# 01-mcu.net
KiCad netlist of a schematic drawn in EAGLE
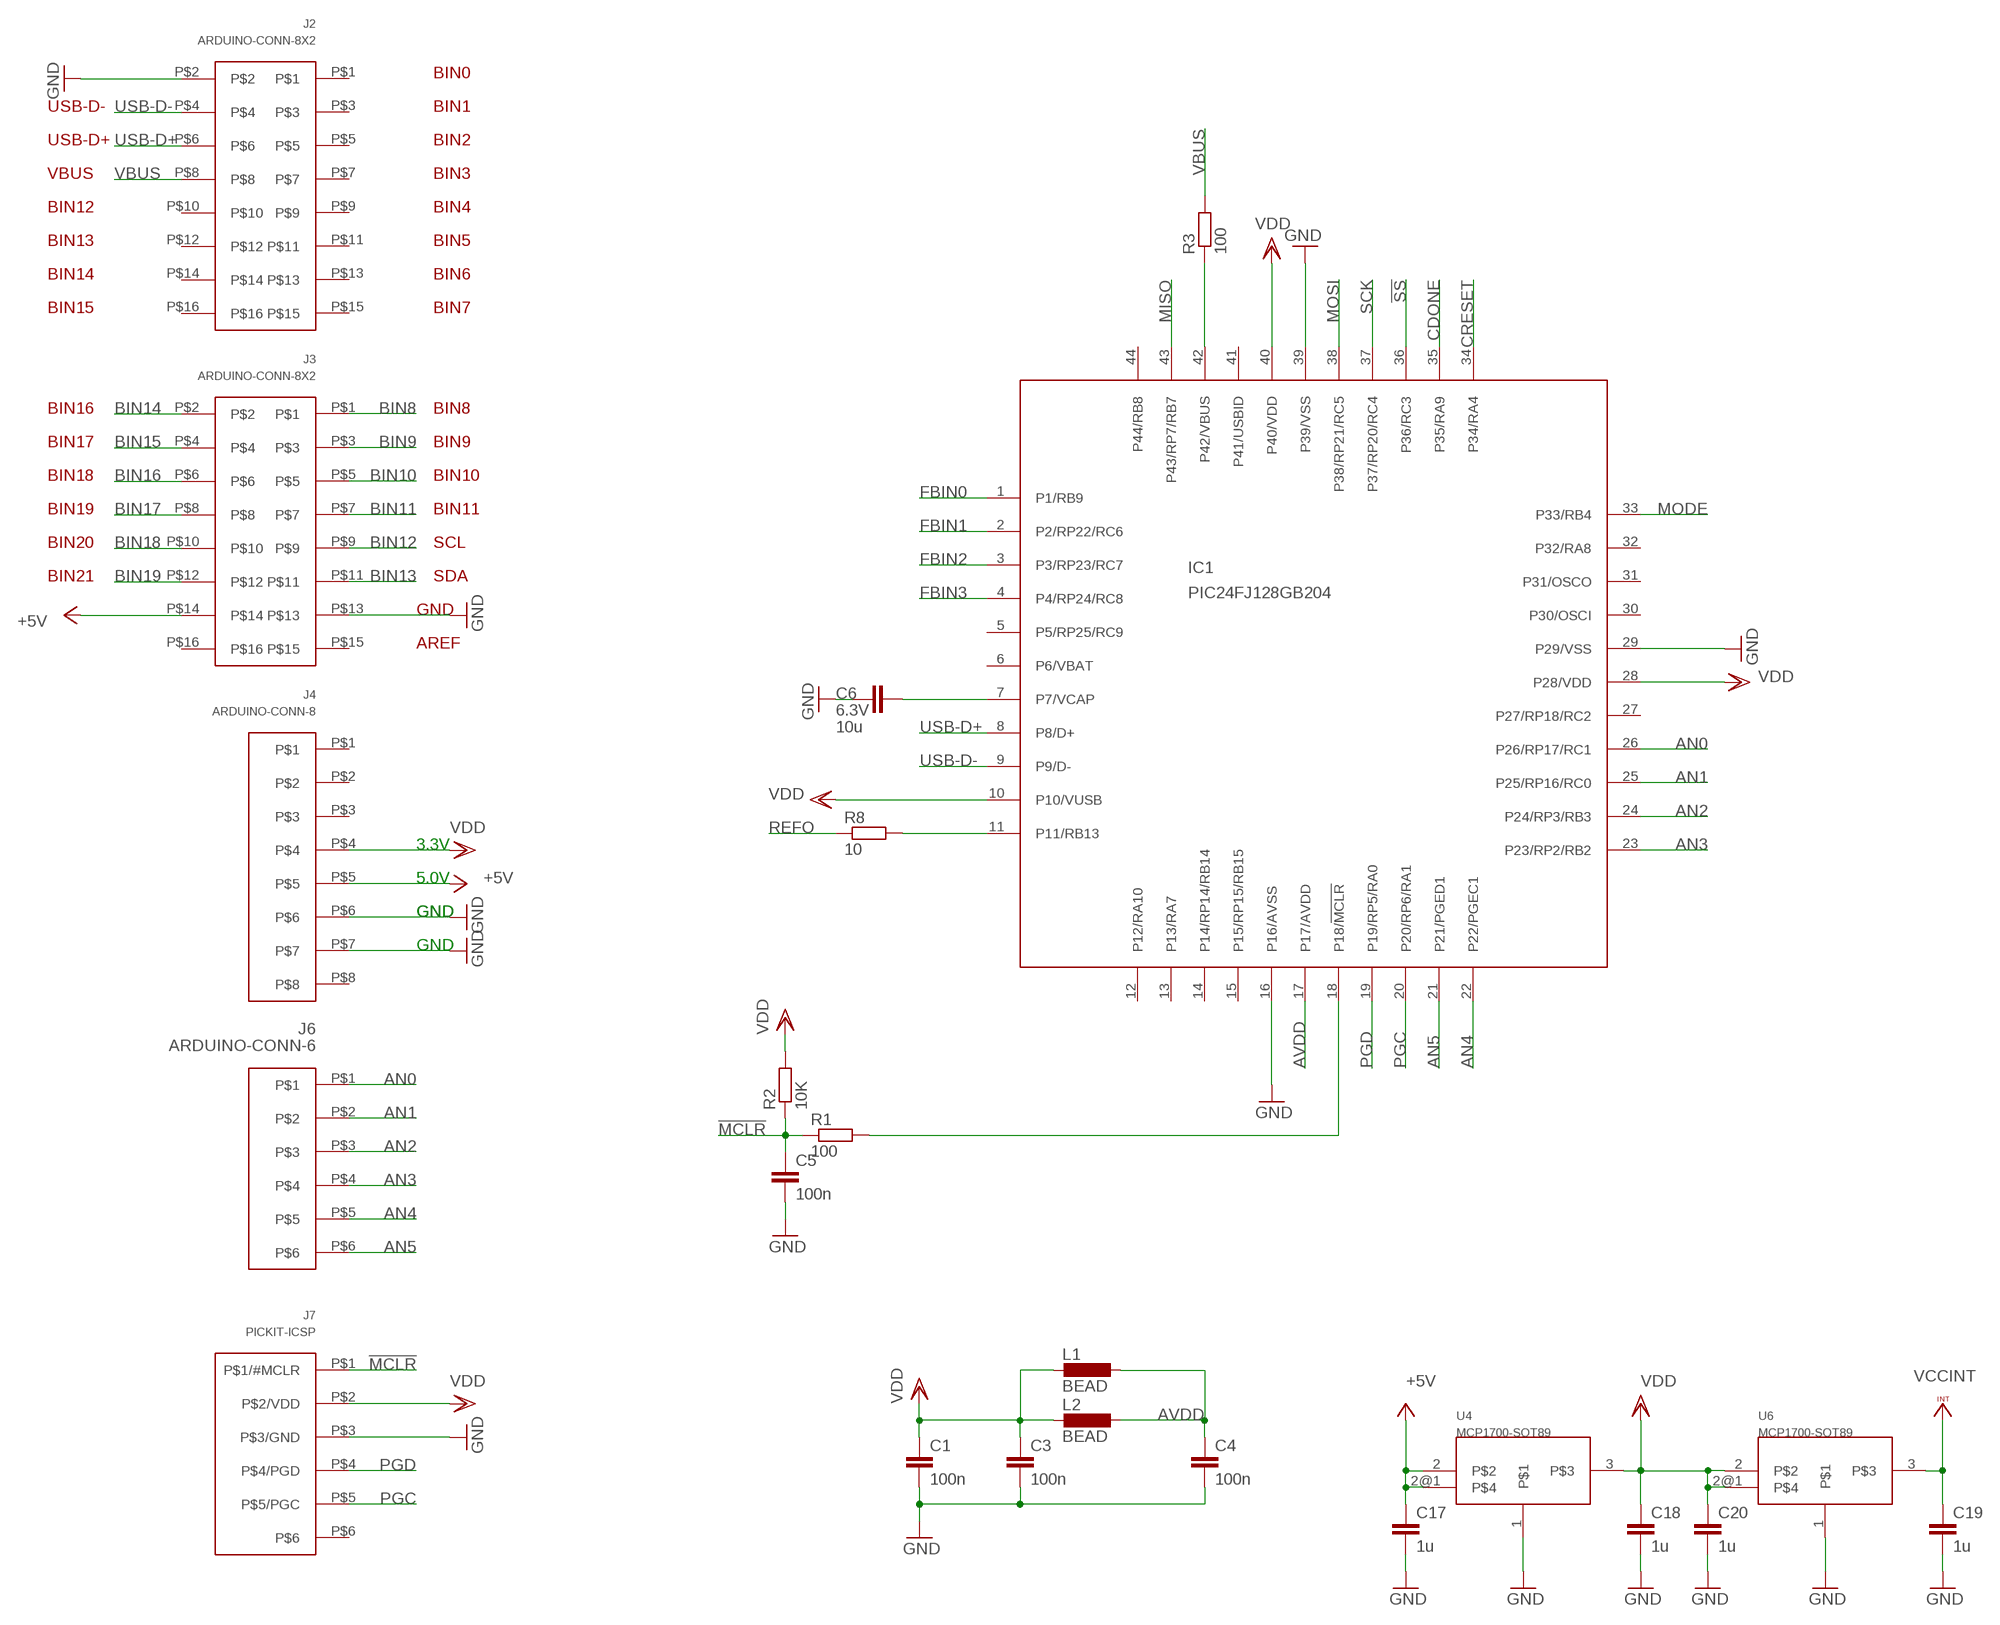
[diagram p0: schematic, sheet 1, part 1 of 2]
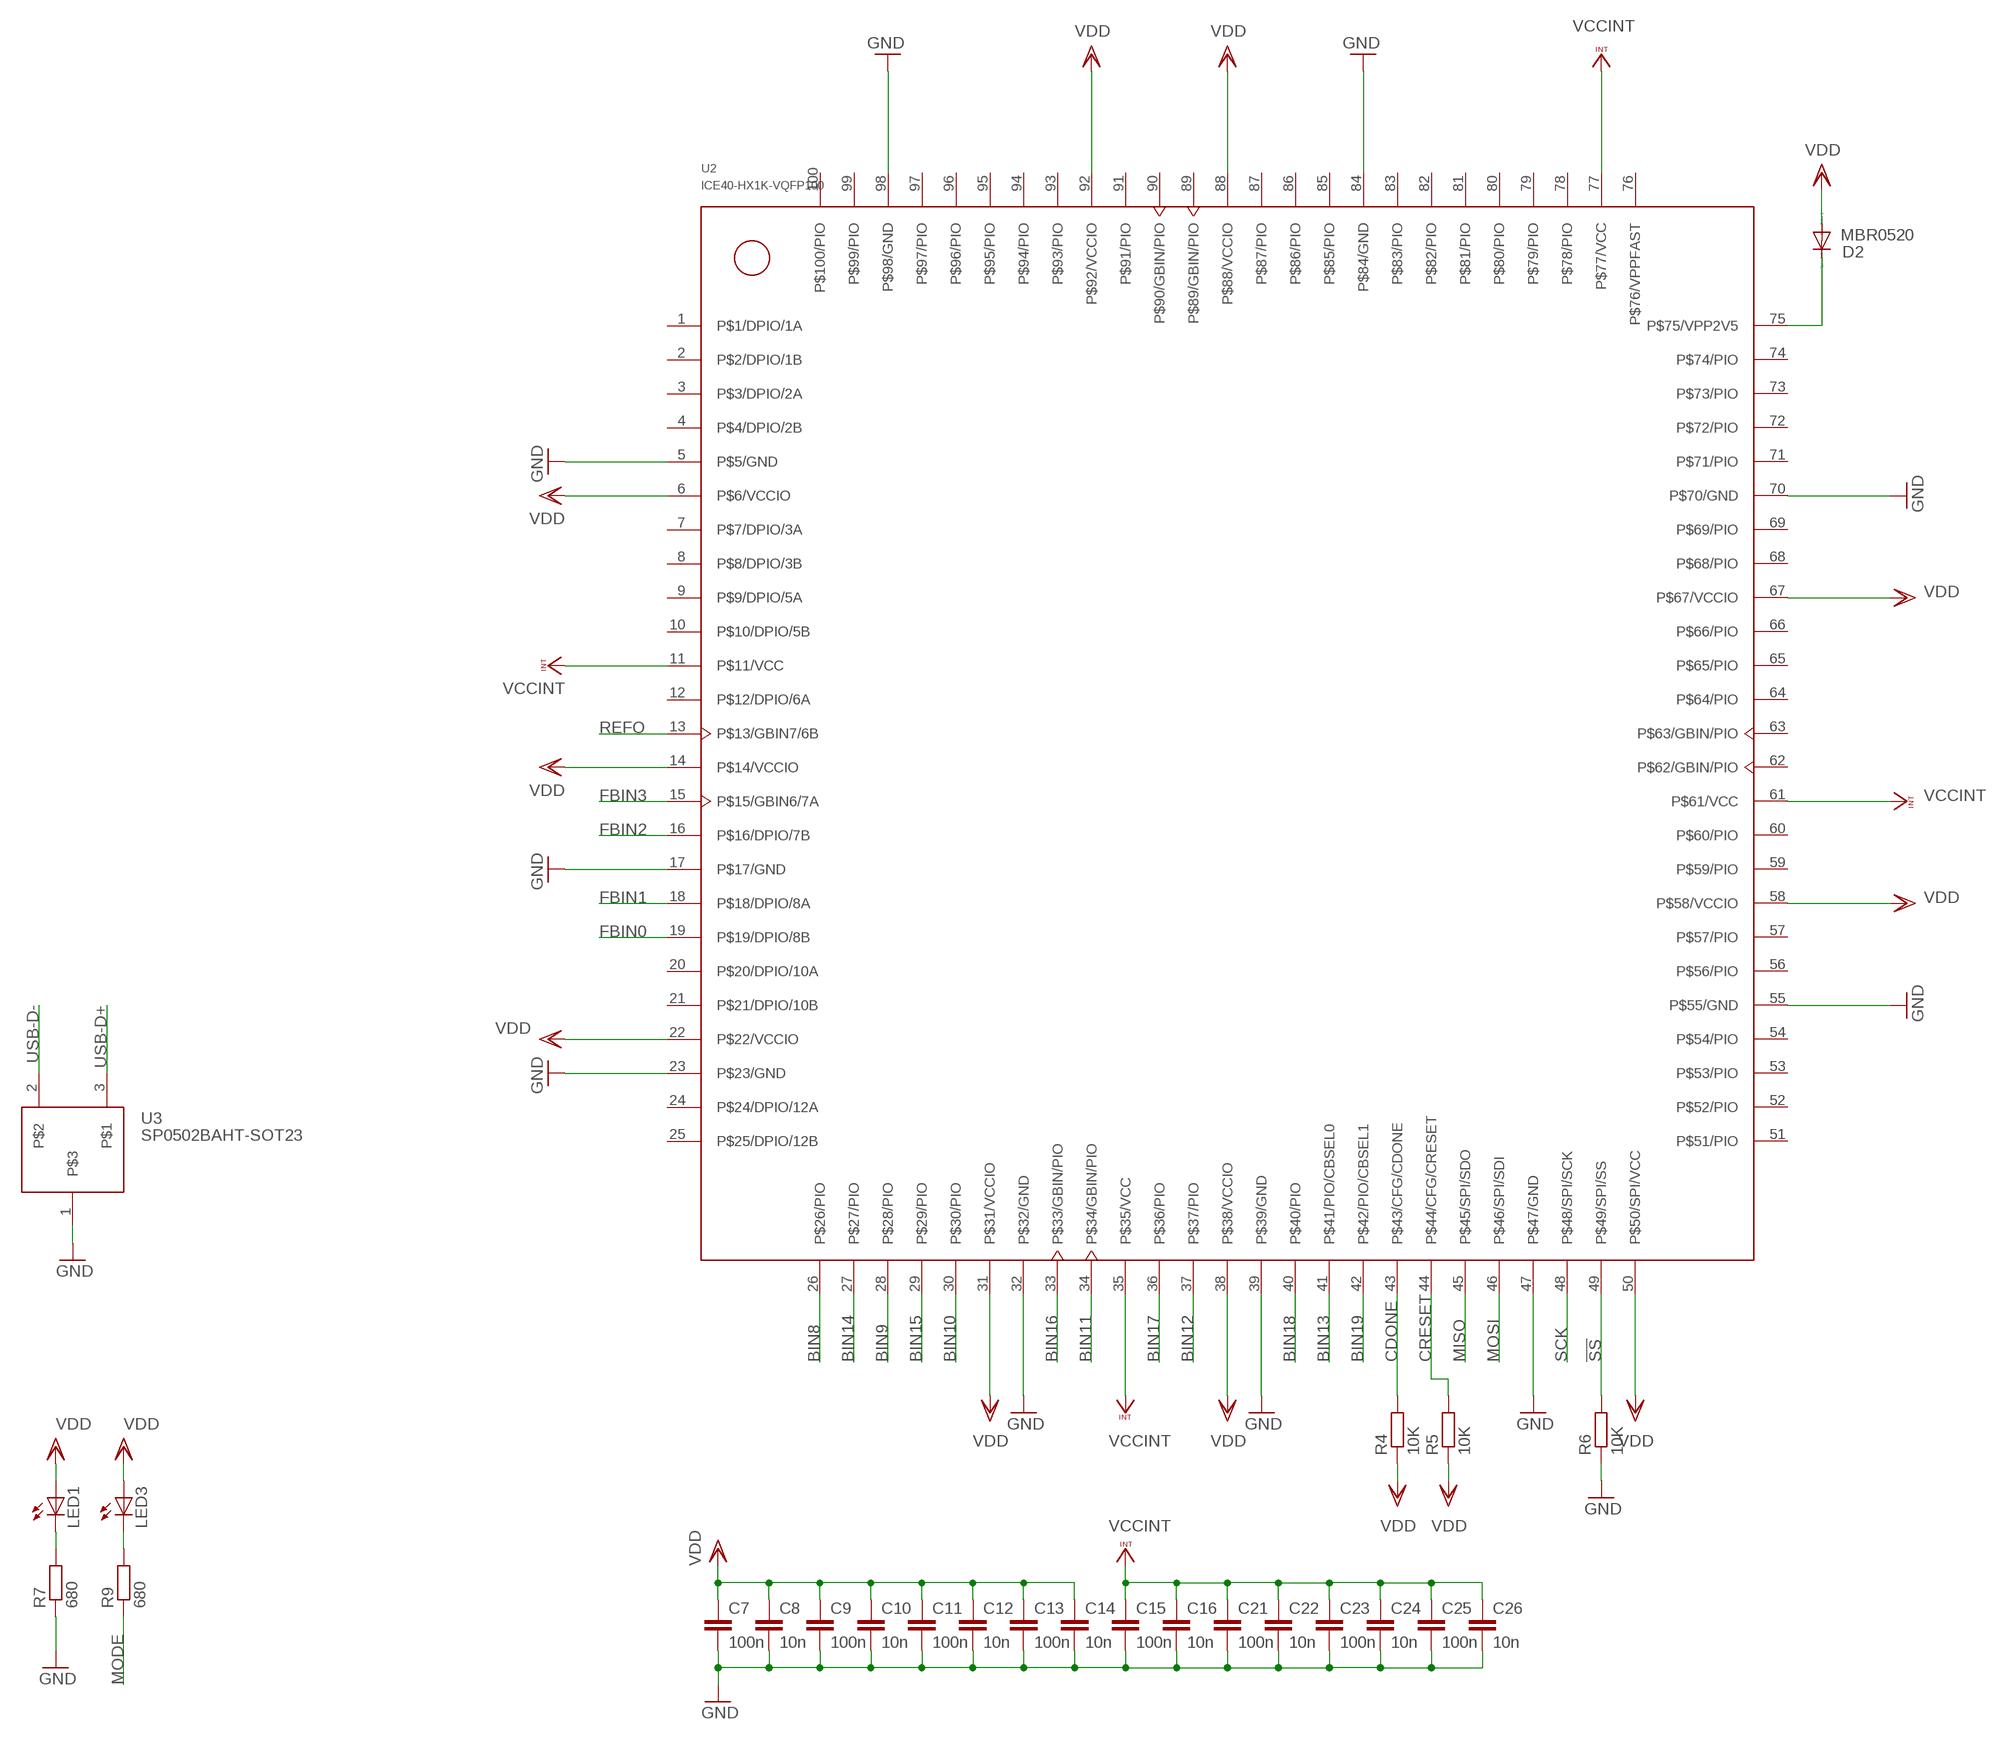
[diagram p1: schematic, sheet 1, part 2 of 2]

(export (version "E")
  (design (tool "Eeschema 10.0.6"))
  (components
    (comp (ref "C1")
      (value "100n")
      (footprint "eagle-import:C0805")
      (libsource (lib "eagle-import") (part "C-EUC0805"))
    )
    (comp (ref "C3")
      (value "100n")
      (footprint "eagle-import:C0805")
      (libsource (lib "eagle-import") (part "C-EUC0805"))
    )
    (comp (ref "C4")
      (value "100n")
      (footprint "eagle-import:C0805")
      (libsource (lib "eagle-import") (part "C-EUC0805"))
    )
    (comp (ref "C5")
      (value "100n")
      (footprint "eagle-import:C0805")
      (libsource (lib "eagle-import") (part "C-EUC0805"))
    )
    (comp (ref "C6")
      (value "10u")
      (footprint "eagle-import:C0805")
      (fields (field (name "RATING") "6.3V"))
      (libsource (lib "eagle-import") (part "C-EUC0805"))
    )
    (comp (ref "C7")
      (value "100n")
      (footprint "eagle-import:C0805")
      (libsource (lib "eagle-import") (part "C-EUC0805"))
    )
    (comp (ref "C8")
      (value "10n")
      (footprint "eagle-import:C0805")
      (libsource (lib "eagle-import") (part "C-EUC0805"))
    )
    (comp (ref "C9")
      (value "100n")
      (footprint "eagle-import:C0805")
      (libsource (lib "eagle-import") (part "C-EUC0805"))
    )
    (comp (ref "C10")
      (value "10n")
      (footprint "eagle-import:C0805")
      (libsource (lib "eagle-import") (part "C-EUC0805"))
    )
    (comp (ref "C11")
      (value "100n")
      (footprint "eagle-import:C0805")
      (libsource (lib "eagle-import") (part "C-EUC0805"))
    )
    (comp (ref "C12")
      (value "10n")
      (footprint "eagle-import:C0805")
      (libsource (lib "eagle-import") (part "C-EUC0805"))
    )
    (comp (ref "C13")
      (value "100n")
      (footprint "eagle-import:C0805")
      (libsource (lib "eagle-import") (part "C-EUC0805"))
    )
    (comp (ref "C14")
      (value "10n")
      (footprint "eagle-import:C0805")
      (libsource (lib "eagle-import") (part "C-EUC0805"))
    )
    (comp (ref "C15")
      (value "100n")
      (footprint "eagle-import:C0805")
      (libsource (lib "eagle-import") (part "C-EUC0805"))
    )
    (comp (ref "C16")
      (value "10n")
      (footprint "eagle-import:C0805")
      (libsource (lib "eagle-import") (part "C-EUC0805"))
    )
    (comp (ref "C17")
      (value "1u")
      (footprint "eagle-import:C0805")
      (libsource (lib "eagle-import") (part "C-EUC0805"))
    )
    (comp (ref "C18")
      (value "1u")
      (footprint "eagle-import:C0805")
      (libsource (lib "eagle-import") (part "C-EUC0805"))
    )
    (comp (ref "C19")
      (value "1u")
      (footprint "eagle-import:C0805")
      (libsource (lib "eagle-import") (part "C-EUC0805"))
    )
    (comp (ref "C20")
      (value "1u")
      (footprint "eagle-import:C0805")
      (libsource (lib "eagle-import") (part "C-EUC0805"))
    )
    (comp (ref "C21")
      (value "100n")
      (footprint "eagle-import:C0805")
      (libsource (lib "eagle-import") (part "C-EUC0805"))
    )
    (comp (ref "C22")
      (value "10n")
      (footprint "eagle-import:C0805")
      (libsource (lib "eagle-import") (part "C-EUC0805"))
    )
    (comp (ref "C23")
      (value "100n")
      (footprint "eagle-import:C0805")
      (libsource (lib "eagle-import") (part "C-EUC0805"))
    )
    (comp (ref "C24")
      (value "10n")
      (footprint "eagle-import:C0805")
      (libsource (lib "eagle-import") (part "C-EUC0805"))
    )
    (comp (ref "C25")
      (value "100n")
      (footprint "eagle-import:C0805")
      (libsource (lib "eagle-import") (part "C-EUC0805"))
    )
    (comp (ref "C26")
      (value "10n")
      (footprint "eagle-import:C0805")
      (libsource (lib "eagle-import") (part "C-EUC0805"))
    )
    (comp (ref "D2")
      (value "MBR0520")
      (footprint "eagle-import:MBR0520-SOD-123_MINI-SMA")
      (libsource (lib "eagle-import") (part "MBR0520"))
    )
    (comp (ref "IC1")
      (value "PIC24FJ128GB204")
      (footprint "eagle-import:TQFP44")
      (libsource (lib "eagle-import") (part "PIC24FJ128GB204"))
    )
    (comp (ref "J2")
      (value "ARDUINO-CONN-8X2")
      (footprint "eagle-import:ARDUINO-CONN-8X2")
      (libsource (lib "eagle-import") (part "ARDUINO-CONN-8X2"))
    )
    (comp (ref "J3")
      (value "ARDUINO-CONN-8X2")
      (footprint "eagle-import:ARDUINO-CONN-8X2")
      (libsource (lib "eagle-import") (part "ARDUINO-CONN-8X2"))
    )
    (comp (ref "J4")
      (value "ARDUINO-CONN-8")
      (footprint "eagle-import:ARDUINO-CONN-8")
      (libsource (lib "eagle-import") (part "ARDUINO-CONN-8"))
    )
    (comp (ref "J6")
      (value "ARDUINO-CONN-6")
      (footprint "eagle-import:ARDUINO-CONN-6")
      (libsource (lib "eagle-import") (part "ARDUINO-CONN-6"))
    )
    (comp (ref "J7")
      (value "PICKIT-ICSP")
      (footprint "eagle-import:PICKIT-ICSP")
      (libsource (lib "eagle-import") (part "PICKIT-ICSP"))
    )
    (comp (ref "L1")
      (value "BEAD")
      (footprint "eagle-import:L0805")
      (libsource (lib "eagle-import") (part "BEAD"))
    )
    (comp (ref "L2")
      (value "BEAD")
      (footprint "eagle-import:L0805")
      (libsource (lib "eagle-import") (part "BEAD"))
    )
    (comp (ref "LED1")
      (value "LEDCHIP-LED0805")
      (footprint "eagle-import:CHIP-LED0805")
      (libsource (lib "eagle-import") (part "LEDCHIP-LED0805"))
    )
    (comp (ref "LED3")
      (value "LEDCHIP-LED0805")
      (footprint "eagle-import:CHIP-LED0805")
      (libsource (lib "eagle-import") (part "LEDCHIP-LED0805"))
    )
    (comp (ref "R1")
      (value "100")
      (footprint "eagle-import:R0805")
      (libsource (lib "eagle-import") (part "R-EU_R0805"))
    )
    (comp (ref "R2")
      (value "10K")
      (footprint "eagle-import:R0805")
      (libsource (lib "eagle-import") (part "R-EU_R0805"))
    )
    (comp (ref "R3")
      (value "100")
      (footprint "eagle-import:R0805")
      (libsource (lib "eagle-import") (part "R-EU_R0805"))
    )
    (comp (ref "R4")
      (value "10K")
      (footprint "eagle-import:R0805")
      (libsource (lib "eagle-import") (part "R-EU_R0805"))
    )
    (comp (ref "R5")
      (value "10K")
      (footprint "eagle-import:R0805")
      (libsource (lib "eagle-import") (part "R-EU_R0805"))
    )
    (comp (ref "R6")
      (value "10K")
      (footprint "eagle-import:R0805")
      (libsource (lib "eagle-import") (part "R-EU_R0805"))
    )
    (comp (ref "R7")
      (value "680")
      (footprint "eagle-import:R0805")
      (libsource (lib "eagle-import") (part "R-EU_R0805"))
    )
    (comp (ref "R8")
      (value "10")
      (footprint "eagle-import:R0805")
      (libsource (lib "eagle-import") (part "R-EU_R0805"))
    )
    (comp (ref "R9")
      (value "680")
      (footprint "eagle-import:R0805")
      (libsource (lib "eagle-import") (part "R-EU_R0805"))
    )
    (comp (ref "U2")
      (value "ICE40-HX1K-VQFP100")
      (footprint "eagle-import:TQFP100-14X14")
      (libsource (lib "eagle-import") (part "ICE40-HX1K-VQFP100"))
    )
    (comp (ref "U3")
      (value "SP0502BAHT-SOT23")
      (footprint "eagle-import:SOT23")
      (libsource (lib "eagle-import") (part "SP0502BAHT-SOT23"))
    )
    (comp (ref "U4")
      (value "MCP1700-SOT89")
      (footprint "eagle-import:MCP1700-SOT89")
      (libsource (lib "eagle-import") (part "MCP1700-SOT89"))
    )
    (comp (ref "U6")
      (value "MCP1700-SOT89")
      (footprint "eagle-import:MCP1700-SOT89")
      (libsource (lib "eagle-import") (part "MCP1700-SOT89"))
    )
  )
  (nets
    (net (code "1") (name "+5V") (class "Default")
      (node (ref "C17") (pin "1") (pinfunction "1_1") (pintype "passive"))
      (node (ref "J3") (pin "P$14") (pinfunction "P$14_P$14") (pintype "bidirectional"))
      (node (ref "J4") (pin "P$5") (pinfunction "P$5_P$5") (pintype "bidirectional"))
      (node (ref "U4") (pin "2") (pinfunction "P$2_2") (pintype "bidirectional"))
      (node (ref "U4") (pin "2@1") (pinfunction "P$4_2@1") (pintype "bidirectional"))
    )
    (net (code "2") (name "/AN0") (class "Default")
      (node (ref "IC1") (pin "26") (pinfunction "P26/RP17/RC1_26") (pintype "bidirectional"))
      (node (ref "J6") (pin "P$1") (pinfunction "P$1_P$1") (pintype "bidirectional"))
    )
    (net (code "3") (name "/AN1") (class "Default")
      (node (ref "IC1") (pin "25") (pinfunction "P25/RP16/RC0_25") (pintype "bidirectional"))
      (node (ref "J6") (pin "P$2") (pinfunction "P$2_P$2") (pintype "bidirectional"))
    )
    (net (code "4") (name "/AN2") (class "Default")
      (node (ref "IC1") (pin "24") (pinfunction "P24/RP3/RB3_24") (pintype "bidirectional"))
      (node (ref "J6") (pin "P$3") (pinfunction "P$3_P$3") (pintype "bidirectional"))
    )
    (net (code "5") (name "/AN3") (class "Default")
      (node (ref "IC1") (pin "23") (pinfunction "P23/RP2/RB2_23") (pintype "bidirectional"))
      (node (ref "J6") (pin "P$4") (pinfunction "P$4_P$4") (pintype "bidirectional"))
    )
    (net (code "6") (name "/AN4") (class "Default")
      (node (ref "IC1") (pin "22") (pinfunction "P22/PGEC1_22") (pintype "bidirectional"))
      (node (ref "J6") (pin "P$5") (pinfunction "P$5_P$5") (pintype "bidirectional"))
    )
    (net (code "7") (name "/AN5") (class "Default")
      (node (ref "IC1") (pin "21") (pinfunction "P21/PGED1_21") (pintype "bidirectional"))
      (node (ref "J6") (pin "P$6") (pinfunction "P$6_P$6") (pintype "bidirectional"))
    )
    (net (code "8") (name "/AVDD") (class "Default")
      (node (ref "C4") (pin "1") (pinfunction "1_1") (pintype "passive"))
      (node (ref "IC1") (pin "17") (pinfunction "P17/AVDD_17") (pintype "power_in"))
      (node (ref "L1") (pin "2") (pinfunction "2_2") (pintype "passive"))
      (node (ref "L2") (pin "2") (pinfunction "2_2") (pintype "passive"))
    )
    (net (code "9") (name "/BIN8") (class "Default")
      (node (ref "J3") (pin "P$1") (pinfunction "P$1_P$1") (pintype "bidirectional"))
      (node (ref "U2") (pin "26") (pinfunction "P$26/PIO_26") (pintype "bidirectional"))
    )
    (net (code "10") (name "/BIN9") (class "Default")
      (node (ref "J3") (pin "P$3") (pinfunction "P$3_P$3") (pintype "bidirectional"))
      (node (ref "U2") (pin "28") (pinfunction "P$28/PIO_28") (pintype "bidirectional"))
    )
    (net (code "11") (name "/BIN10") (class "Default")
      (node (ref "J3") (pin "P$5") (pinfunction "P$5_P$5") (pintype "bidirectional"))
      (node (ref "U2") (pin "30") (pinfunction "P$30/PIO_30") (pintype "bidirectional"))
    )
    (net (code "12") (name "/BIN11") (class "Default")
      (node (ref "J3") (pin "P$7") (pinfunction "P$7_P$7") (pintype "bidirectional"))
      (node (ref "U2") (pin "34") (pinfunction "P$34/GBIN/PIO_34") (pintype "bidirectional"))
    )
    (net (code "13") (name "/BIN12") (class "Default")
      (node (ref "J3") (pin "P$9") (pinfunction "P$9_P$9") (pintype "bidirectional"))
      (node (ref "U2") (pin "37") (pinfunction "P$37/PIO_37") (pintype "bidirectional"))
    )
    (net (code "14") (name "/BIN13") (class "Default")
      (node (ref "J3") (pin "P$11") (pinfunction "P$11_P$11") (pintype "bidirectional"))
      (node (ref "U2") (pin "41") (pinfunction "P$41/PIO/CBSEL0_41") (pintype "bidirectional"))
    )
    (net (code "15") (name "/BIN14") (class "Default")
      (node (ref "J3") (pin "P$2") (pinfunction "P$2_P$2") (pintype "bidirectional"))
      (node (ref "U2") (pin "27") (pinfunction "P$27/PIO_27") (pintype "bidirectional"))
    )
    (net (code "16") (name "/BIN15") (class "Default")
      (node (ref "J3") (pin "P$4") (pinfunction "P$4_P$4") (pintype "bidirectional"))
      (node (ref "U2") (pin "29") (pinfunction "P$29/PIO_29") (pintype "bidirectional"))
    )
    (net (code "17") (name "/BIN16") (class "Default")
      (node (ref "J3") (pin "P$6") (pinfunction "P$6_P$6") (pintype "bidirectional"))
      (node (ref "U2") (pin "33") (pinfunction "P$33/GBIN/PIO_33") (pintype "bidirectional"))
    )
    (net (code "18") (name "/BIN17") (class "Default")
      (node (ref "J3") (pin "P$8") (pinfunction "P$8_P$8") (pintype "bidirectional"))
      (node (ref "U2") (pin "36") (pinfunction "P$36/PIO_36") (pintype "bidirectional"))
    )
    (net (code "19") (name "/BIN18") (class "Default")
      (node (ref "J3") (pin "P$10") (pinfunction "P$10_P$10") (pintype "bidirectional"))
      (node (ref "U2") (pin "40") (pinfunction "P$40/PIO_40") (pintype "bidirectional"))
    )
    (net (code "20") (name "/BIN19") (class "Default")
      (node (ref "J3") (pin "P$12") (pinfunction "P$12_P$12") (pintype "bidirectional"))
      (node (ref "U2") (pin "42") (pinfunction "P$42/PIO/CBSEL1_42") (pintype "bidirectional"))
    )
    (net (code "21") (name "/CDONE") (class "Default")
      (node (ref "IC1") (pin "35") (pinfunction "P35/RA9_35") (pintype "input"))
      (node (ref "R4") (pin "2") (pinfunction "2_2") (pintype "passive"))
      (node (ref "U2") (pin "43") (pinfunction "P$43/CFG/CDONE_43") (pintype "bidirectional"))
    )
    (net (code "22") (name "/CRESET") (class "Default")
      (node (ref "IC1") (pin "34") (pinfunction "P34/RA4_34") (pintype "bidirectional"))
      (node (ref "R5") (pin "2") (pinfunction "2_2") (pintype "passive"))
      (node (ref "U2") (pin "44") (pinfunction "P$44/CFG/CRESET_44") (pintype "bidirectional"))
    )
    (net (code "23") (name "/FBIN0") (class "Default")
      (node (ref "IC1") (pin "1") (pinfunction "P1/RB9_1") (pintype "bidirectional"))
      (node (ref "U2") (pin "19") (pinfunction "P$19/DPIO/8B_19") (pintype "bidirectional"))
    )
    (net (code "24") (name "/FBIN1") (class "Default")
      (node (ref "IC1") (pin "2") (pinfunction "P2/RP22/RC6_2") (pintype "bidirectional"))
      (node (ref "U2") (pin "18") (pinfunction "P$18/DPIO/8A_18") (pintype "bidirectional"))
    )
    (net (code "25") (name "/FBIN2") (class "Default")
      (node (ref "IC1") (pin "3") (pinfunction "P3/RP23/RC7_3") (pintype "bidirectional"))
      (node (ref "U2") (pin "16") (pinfunction "P$16/DPIO/7B_16") (pintype "bidirectional"))
    )
    (net (code "26") (name "/FBIN3") (class "Default")
      (node (ref "IC1") (pin "4") (pinfunction "P4/RP24/RC8_4") (pintype "bidirectional"))
      (node (ref "U2") (pin "15") (pinfunction "P$15/GBIN6/7A_15") (pintype "bidirectional"))
    )
    (net (code "27") (name "/MISO") (class "Default")
      (node (ref "IC1") (pin "43") (pinfunction "P43/RP7/RB7_43") (pintype "bidirectional"))
      (node (ref "U2") (pin "45") (pinfunction "P$45/SPI/SDO_45") (pintype "bidirectional"))
    )
    (net (code "28") (name "/MODE") (class "Default")
      (node (ref "IC1") (pin "33") (pinfunction "P33/RB4_33") (pintype "bidirectional"))
      (node (ref "R9") (pin "1") (pinfunction "1_1") (pintype "passive"))
    )
    (net (code "29") (name "/MOSI") (class "Default")
      (node (ref "IC1") (pin "38") (pinfunction "P38/RP21/RC5_38") (pintype "bidirectional"))
      (node (ref "U2") (pin "46") (pinfunction "P$46/SPI/SDI_46") (pintype "bidirectional"))
    )
    (net (code "30") (name "/PGC") (class "Default")
      (node (ref "IC1") (pin "20") (pinfunction "P20/RP6/RA1_20") (pintype "bidirectional"))
      (node (ref "J7") (pin "P$5") (pinfunction "P$5/PGC_P$5") (pintype "bidirectional"))
    )
    (net (code "31") (name "/PGD") (class "Default")
      (node (ref "IC1") (pin "19") (pinfunction "P19/RP5/RA0_19") (pintype "bidirectional"))
      (node (ref "J7") (pin "P$4") (pinfunction "P$4/PGD_P$4") (pintype "bidirectional"))
    )
    (net (code "32") (name "/REFO") (class "Default")
      (node (ref "R8") (pin "1") (pinfunction "1_1") (pintype "passive"))
      (node (ref "U2") (pin "13") (pinfunction "P$13/GBIN7/6B_13") (pintype "bidirectional"))
    )
    (net (code "33") (name "/SCK") (class "Default")
      (node (ref "IC1") (pin "37") (pinfunction "P37/RP20/RC4_37") (pintype "bidirectional"))
      (node (ref "U2") (pin "48") (pinfunction "P$48/SPI/SCK_48") (pintype "bidirectional"))
    )
    (net (code "34") (name "/USB-D+") (class "Default")
      (node (ref "IC1") (pin "8") (pinfunction "P8/D+_8") (pintype "bidirectional"))
      (node (ref "J2") (pin "P$6") (pinfunction "P$6_P$6") (pintype "bidirectional"))
      (node (ref "U3") (pin "3") (pinfunction "P$1_3") (pintype "bidirectional"))
    )
    (net (code "35") (name "/USB-D-") (class "Default")
      (node (ref "IC1") (pin "9") (pinfunction "P9/D-_9") (pintype "bidirectional"))
      (node (ref "J2") (pin "P$4") (pinfunction "P$4_P$4") (pintype "bidirectional"))
      (node (ref "U3") (pin "2") (pinfunction "P$2_2") (pintype "bidirectional"))
    )
    (net (code "36") (name "/VBUS") (class "Default")
      (node (ref "J2") (pin "P$8") (pinfunction "P$8_P$8") (pintype "bidirectional"))
      (node (ref "R3") (pin "2") (pinfunction "2_2") (pintype "passive"))
    )
    (net (code "37") (name "/~{MCLR}") (class "Default")
      (node (ref "C5") (pin "1") (pinfunction "1_1") (pintype "passive"))
      (node (ref "J7") (pin "P$1") (pinfunction "P$1/#MCLR_P$1") (pintype "bidirectional"))
      (node (ref "R1") (pin "1") (pinfunction "1_1") (pintype "passive"))
      (node (ref "R2") (pin "1") (pinfunction "1_1") (pintype "passive"))
    )
    (net (code "38") (name "/~{SS}") (class "Default")
      (node (ref "IC1") (pin "36") (pinfunction "P36/RC3_36") (pintype "bidirectional"))
      (node (ref "R6") (pin "2") (pinfunction "2_2") (pintype "passive"))
      (node (ref "U2") (pin "49") (pinfunction "P$49/SPI/SS_49") (pintype "bidirectional"))
    )
    (net (code "39") (name "GND") (class "Default")
      (node (ref "C1") (pin "2") (pinfunction "2_2") (pintype "passive"))
      (node (ref "C10") (pin "2") (pinfunction "2_2") (pintype "passive"))
      (node (ref "C11") (pin "2") (pinfunction "2_2") (pintype "passive"))
      (node (ref "C12") (pin "2") (pinfunction "2_2") (pintype "passive"))
      (node (ref "C13") (pin "2") (pinfunction "2_2") (pintype "passive"))
      (node (ref "C14") (pin "2") (pinfunction "2_2") (pintype "passive"))
      (node (ref "C15") (pin "2") (pinfunction "2_2") (pintype "passive"))
      (node (ref "C16") (pin "2") (pinfunction "2_2") (pintype "passive"))
      (node (ref "C17") (pin "2") (pinfunction "2_2") (pintype "passive"))
      (node (ref "C18") (pin "2") (pinfunction "2_2") (pintype "passive"))
      (node (ref "C19") (pin "2") (pinfunction "2_2") (pintype "passive"))
      (node (ref "C20") (pin "2") (pinfunction "2_2") (pintype "passive"))
      (node (ref "C21") (pin "2") (pinfunction "2_2") (pintype "passive"))
      (node (ref "C22") (pin "2") (pinfunction "2_2") (pintype "passive"))
      (node (ref "C23") (pin "2") (pinfunction "2_2") (pintype "passive"))
      (node (ref "C24") (pin "2") (pinfunction "2_2") (pintype "passive"))
      (node (ref "C25") (pin "2") (pinfunction "2_2") (pintype "passive"))
      (node (ref "C26") (pin "2") (pinfunction "2_2") (pintype "passive"))
      (node (ref "C3") (pin "2") (pinfunction "2_2") (pintype "passive"))
      (node (ref "C4") (pin "2") (pinfunction "2_2") (pintype "passive"))
      (node (ref "C5") (pin "2") (pinfunction "2_2") (pintype "passive"))
      (node (ref "C6") (pin "1") (pinfunction "1_1") (pintype "passive"))
      (node (ref "C7") (pin "2") (pinfunction "2_2") (pintype "passive"))
      (node (ref "C8") (pin "2") (pinfunction "2_2") (pintype "passive"))
      (node (ref "C9") (pin "2") (pinfunction "2_2") (pintype "passive"))
      (node (ref "IC1") (pin "16") (pinfunction "P16/AVSS_16") (pintype "power_in"))
      (node (ref "IC1") (pin "29") (pinfunction "P29/VSS_29") (pintype "power_in"))
      (node (ref "IC1") (pin "39") (pinfunction "P39/VSS_39") (pintype "power_in"))
      (node (ref "J2") (pin "P$2") (pinfunction "P$2_P$2") (pintype "bidirectional"))
      (node (ref "J3") (pin "P$13") (pinfunction "P$13_P$13") (pintype "bidirectional"))
      (node (ref "J4") (pin "P$6") (pinfunction "P$6_P$6") (pintype "bidirectional"))
      (node (ref "J4") (pin "P$7") (pinfunction "P$7_P$7") (pintype "bidirectional"))
      (node (ref "J7") (pin "P$3") (pinfunction "P$3/GND_P$3") (pintype "bidirectional"))
      (node (ref "R6") (pin "1") (pinfunction "1_1") (pintype "passive"))
      (node (ref "R7") (pin "1") (pinfunction "1_1") (pintype "passive"))
      (node (ref "U2") (pin "17") (pinfunction "P$17/GND_17") (pintype "bidirectional"))
      (node (ref "U2") (pin "23") (pinfunction "P$23/GND_23") (pintype "bidirectional"))
      (node (ref "U2") (pin "32") (pinfunction "P$32/GND_32") (pintype "bidirectional"))
      (node (ref "U2") (pin "39") (pinfunction "P$39/GND_39") (pintype "bidirectional"))
      (node (ref "U2") (pin "47") (pinfunction "P$47/GND_47") (pintype "bidirectional"))
      (node (ref "U2") (pin "5") (pinfunction "P$5/GND_5") (pintype "bidirectional"))
      (node (ref "U2") (pin "55") (pinfunction "P$55/GND_55") (pintype "bidirectional"))
      (node (ref "U2") (pin "70") (pinfunction "P$70/GND_70") (pintype "bidirectional"))
      (node (ref "U2") (pin "84") (pinfunction "P$84/GND_84") (pintype "bidirectional"))
      (node (ref "U2") (pin "98") (pinfunction "P$98/GND_98") (pintype "bidirectional"))
      (node (ref "U3") (pin "1") (pinfunction "P$3_1") (pintype "bidirectional"))
      (node (ref "U4") (pin "1") (pinfunction "P$1_1") (pintype "bidirectional"))
      (node (ref "U6") (pin "1") (pinfunction "P$1_1") (pintype "bidirectional"))
    )
    (net (code "40") (name "Net-(IC1-P7{slash}VCAP)") (class "Default")
      (node (ref "C6") (pin "2") (pinfunction "2_2") (pintype "passive"))
      (node (ref "IC1") (pin "7") (pinfunction "P7/VCAP_7") (pintype "power_in"))
    )
    (net (code "41") (name "Net-(IC1-P11{slash}RB13)") (class "Default")
      (node (ref "IC1") (pin "11") (pinfunction "P11/RB13_11") (pintype "bidirectional"))
      (node (ref "R8") (pin "2") (pinfunction "2_2") (pintype "passive"))
    )
    (net (code "42") (name "Net-(IC1-P18{slash}~{MCLR})") (class "Default")
      (node (ref "IC1") (pin "18") (pinfunction "P18/~{MCLR}_18") (pintype "bidirectional"))
      (node (ref "R1") (pin "2") (pinfunction "2_2") (pintype "passive"))
    )
    (net (code "43") (name "Net-(IC1-P42{slash}VBUS)") (class "Default")
      (node (ref "IC1") (pin "42") (pinfunction "P42/VBUS_42") (pintype "bidirectional"))
      (node (ref "R3") (pin "1") (pinfunction "1_1") (pintype "passive"))
    )
    (net (code "44") (name "Net-(LED1-PadC)") (class "Default")
      (node (ref "LED1") (pin "C") (pinfunction "C_C") (pintype "passive"))
      (node (ref "R7") (pin "2") (pinfunction "2_2") (pintype "passive"))
    )
    (net (code "45") (name "Net-(LED3-PadC)") (class "Default")
      (node (ref "LED3") (pin "C") (pinfunction "C_C") (pintype "passive"))
      (node (ref "R9") (pin "2") (pinfunction "2_2") (pintype "passive"))
    )
    (net (code "46") (name "Net-(U2-P$75{slash}VPP2V5)") (class "Default")
      (node (ref "D2") (pin "C") (pinfunction "C_C") (pintype "passive"))
      (node (ref "U2") (pin "75") (pinfunction "P$75/VPP2V5_75") (pintype "bidirectional"))
    )
    (net (code "47") (name "VCCINT") (class "Default")
      (node (ref "C15") (pin "1") (pinfunction "1_1") (pintype "passive"))
      (node (ref "C16") (pin "1") (pinfunction "1_1") (pintype "passive"))
      (node (ref "C19") (pin "1") (pinfunction "1_1") (pintype "passive"))
      (node (ref "C21") (pin "1") (pinfunction "1_1") (pintype "passive"))
      (node (ref "C22") (pin "1") (pinfunction "1_1") (pintype "passive"))
      (node (ref "C23") (pin "1") (pinfunction "1_1") (pintype "passive"))
      (node (ref "C24") (pin "1") (pinfunction "1_1") (pintype "passive"))
      (node (ref "C25") (pin "1") (pinfunction "1_1") (pintype "passive"))
      (node (ref "C26") (pin "1") (pinfunction "1_1") (pintype "passive"))
      (node (ref "U2") (pin "11") (pinfunction "P$11/VCC_11") (pintype "bidirectional"))
      (node (ref "U2") (pin "35") (pinfunction "P$35/VCC_35") (pintype "bidirectional"))
      (node (ref "U2") (pin "61") (pinfunction "P$61/VCC_61") (pintype "bidirectional"))
      (node (ref "U2") (pin "77") (pinfunction "P$77/VCC_77") (pintype "bidirectional"))
      (node (ref "U6") (pin "3") (pinfunction "P$3_3") (pintype "bidirectional"))
    )
    (net (code "48") (name "VDD") (class "Default")
      (node (ref "C1") (pin "1") (pinfunction "1_1") (pintype "passive"))
      (node (ref "C10") (pin "1") (pinfunction "1_1") (pintype "passive"))
      (node (ref "C11") (pin "1") (pinfunction "1_1") (pintype "passive"))
      (node (ref "C12") (pin "1") (pinfunction "1_1") (pintype "passive"))
      (node (ref "C13") (pin "1") (pinfunction "1_1") (pintype "passive"))
      (node (ref "C14") (pin "1") (pinfunction "1_1") (pintype "passive"))
      (node (ref "C18") (pin "1") (pinfunction "1_1") (pintype "passive"))
      (node (ref "C20") (pin "1") (pinfunction "1_1") (pintype "passive"))
      (node (ref "C3") (pin "1") (pinfunction "1_1") (pintype "passive"))
      (node (ref "C7") (pin "1") (pinfunction "1_1") (pintype "passive"))
      (node (ref "C8") (pin "1") (pinfunction "1_1") (pintype "passive"))
      (node (ref "C9") (pin "1") (pinfunction "1_1") (pintype "passive"))
      (node (ref "D2") (pin "A") (pinfunction "A_A") (pintype "passive"))
      (node (ref "IC1") (pin "10") (pinfunction "P10/VUSB_10") (pintype "bidirectional"))
      (node (ref "IC1") (pin "28") (pinfunction "P28/VDD_28") (pintype "power_in"))
      (node (ref "IC1") (pin "40") (pinfunction "P40/VDD_40") (pintype "power_in"))
      (node (ref "J4") (pin "P$4") (pinfunction "P$4_P$4") (pintype "bidirectional"))
      (node (ref "J7") (pin "P$2") (pinfunction "P$2/VDD_P$2") (pintype "bidirectional"))
      (node (ref "L1") (pin "1") (pinfunction "1_1") (pintype "passive"))
      (node (ref "L2") (pin "1") (pinfunction "1_1") (pintype "passive"))
      (node (ref "LED1") (pin "A") (pinfunction "A_A") (pintype "passive"))
      (node (ref "LED3") (pin "A") (pinfunction "A_A") (pintype "passive"))
      (node (ref "R2") (pin "2") (pinfunction "2_2") (pintype "passive"))
      (node (ref "R4") (pin "1") (pinfunction "1_1") (pintype "passive"))
      (node (ref "R5") (pin "1") (pinfunction "1_1") (pintype "passive"))
      (node (ref "U2") (pin "14") (pinfunction "P$14/VCCIO_14") (pintype "bidirectional"))
      (node (ref "U2") (pin "22") (pinfunction "P$22/VCCIO_22") (pintype "bidirectional"))
      (node (ref "U2") (pin "31") (pinfunction "P$31/VCCIO_31") (pintype "bidirectional"))
      (node (ref "U2") (pin "38") (pinfunction "P$38/VCCIO_38") (pintype "bidirectional"))
      (node (ref "U2") (pin "50") (pinfunction "P$50/SPI/VCC_50") (pintype "bidirectional"))
      (node (ref "U2") (pin "58") (pinfunction "P$58/VCCIO_58") (pintype "bidirectional"))
      (node (ref "U2") (pin "6") (pinfunction "P$6/VCCIO_6") (pintype "bidirectional"))
      (node (ref "U2") (pin "67") (pinfunction "P$67/VCCIO_67") (pintype "bidirectional"))
      (node (ref "U2") (pin "88") (pinfunction "P$88/VCCIO_88") (pintype "bidirectional"))
      (node (ref "U2") (pin "92") (pinfunction "P$92/VCCIO_92") (pintype "bidirectional"))
      (node (ref "U4") (pin "3") (pinfunction "P$3_3") (pintype "bidirectional"))
      (node (ref "U6") (pin "2") (pinfunction "P$2_2") (pintype "bidirectional"))
      (node (ref "U6") (pin "2@1") (pinfunction "P$4_2@1") (pintype "bidirectional"))
    )
    (net (code "49") (name "unconnected-(IC1-P5{slash}RP25{slash}RC9-Pad5)") (class "Default")
      (node (ref "IC1") (pin "5") (pinfunction "P5/RP25/RC9_5") (pintype "bidirectional"))
    )
    (net (code "50") (name "unconnected-(IC1-P6{slash}VBAT-Pad6)") (class "Default")
      (node (ref "IC1") (pin "6") (pinfunction "P6/VBAT_6") (pintype "passive"))
    )
    (net (code "51") (name "unconnected-(IC1-P12{slash}RA10-Pad12)") (class "Default")
      (node (ref "IC1") (pin "12") (pinfunction "P12/RA10_12") (pintype "input"))
    )
    (net (code "52") (name "unconnected-(IC1-P13{slash}RA7-Pad13)") (class "Default")
      (node (ref "IC1") (pin "13") (pinfunction "P13/RA7_13") (pintype "input"))
    )
    (net (code "53") (name "unconnected-(IC1-P14{slash}RP14{slash}RB14-Pad14)") (class "Default")
      (node (ref "IC1") (pin "14") (pinfunction "P14/RP14/RB14_14") (pintype "bidirectional"))
    )
    (net (code "54") (name "unconnected-(IC1-P15{slash}RP15{slash}RB15-Pad15)") (class "Default")
      (node (ref "IC1") (pin "15") (pinfunction "P15/RP15/RB15_15") (pintype "bidirectional"))
    )
    (net (code "55") (name "unconnected-(IC1-P27{slash}RP18{slash}RC2-Pad27)") (class "Default")
      (node (ref "IC1") (pin "27") (pinfunction "P27/RP18/RC2_27") (pintype "bidirectional"))
    )
    (net (code "56") (name "unconnected-(IC1-P30{slash}OSCI-Pad30)") (class "Default")
      (node (ref "IC1") (pin "30") (pinfunction "P30/OSCI_30") (pintype "bidirectional"))
    )
    (net (code "57") (name "unconnected-(IC1-P31{slash}OSCO-Pad31)") (class "Default")
      (node (ref "IC1") (pin "31") (pinfunction "P31/OSCO_31") (pintype "bidirectional"))
    )
    (net (code "58") (name "unconnected-(IC1-P32{slash}RA8-Pad32)") (class "Default")
      (node (ref "IC1") (pin "32") (pinfunction "P32/RA8_32") (pintype "output"))
    )
    (net (code "59") (name "unconnected-(IC1-P41{slash}USBID-Pad41)") (class "Default")
      (node (ref "IC1") (pin "41") (pinfunction "P41/USBID_41") (pintype "bidirectional"))
    )
    (net (code "60") (name "unconnected-(IC1-P44{slash}RB8-Pad44)") (class "Default")
      (node (ref "IC1") (pin "44") (pinfunction "P44/RB8_44") (pintype "bidirectional"))
    )
    (net (code "61") (name "unconnected-(J2-PadP$1)") (class "Default")
      (node (ref "J2") (pin "P$1") (pinfunction "P$1_P$1") (pintype "bidirectional"))
    )
    (net (code "62") (name "unconnected-(J2-PadP$3)") (class "Default")
      (node (ref "J2") (pin "P$3") (pinfunction "P$3_P$3") (pintype "bidirectional"))
    )
    (net (code "63") (name "unconnected-(J2-PadP$5)") (class "Default")
      (node (ref "J2") (pin "P$5") (pinfunction "P$5_P$5") (pintype "bidirectional"))
    )
    (net (code "64") (name "unconnected-(J2-PadP$7)") (class "Default")
      (node (ref "J2") (pin "P$7") (pinfunction "P$7_P$7") (pintype "bidirectional"))
    )
    (net (code "65") (name "unconnected-(J2-PadP$9)") (class "Default")
      (node (ref "J2") (pin "P$9") (pinfunction "P$9_P$9") (pintype "bidirectional"))
    )
    (net (code "66") (name "unconnected-(J2-PadP$10)") (class "Default")
      (node (ref "J2") (pin "P$10") (pinfunction "P$10_P$10") (pintype "bidirectional"))
    )
    (net (code "67") (name "unconnected-(J2-PadP$11)") (class "Default")
      (node (ref "J2") (pin "P$11") (pinfunction "P$11_P$11") (pintype "bidirectional"))
    )
    (net (code "68") (name "unconnected-(J2-PadP$12)") (class "Default")
      (node (ref "J2") (pin "P$12") (pinfunction "P$12_P$12") (pintype "bidirectional"))
    )
    (net (code "69") (name "unconnected-(J2-PadP$13)") (class "Default")
      (node (ref "J2") (pin "P$13") (pinfunction "P$13_P$13") (pintype "bidirectional"))
    )
    (net (code "70") (name "unconnected-(J2-PadP$14)") (class "Default")
      (node (ref "J2") (pin "P$14") (pinfunction "P$14_P$14") (pintype "bidirectional"))
    )
    (net (code "71") (name "unconnected-(J2-PadP$15)") (class "Default")
      (node (ref "J2") (pin "P$15") (pinfunction "P$15_P$15") (pintype "bidirectional"))
    )
    (net (code "72") (name "unconnected-(J2-PadP$16)") (class "Default")
      (node (ref "J2") (pin "P$16") (pinfunction "P$16_P$16") (pintype "bidirectional"))
    )
    (net (code "73") (name "unconnected-(J3-PadP$15)") (class "Default")
      (node (ref "J3") (pin "P$15") (pinfunction "P$15_P$15") (pintype "bidirectional"))
    )
    (net (code "74") (name "unconnected-(J3-PadP$16)") (class "Default")
      (node (ref "J3") (pin "P$16") (pinfunction "P$16_P$16") (pintype "bidirectional"))
    )
    (net (code "75") (name "unconnected-(J4-PadP$1)") (class "Default")
      (node (ref "J4") (pin "P$1") (pinfunction "P$1_P$1") (pintype "bidirectional"))
    )
    (net (code "76") (name "unconnected-(J4-PadP$2)") (class "Default")
      (node (ref "J4") (pin "P$2") (pinfunction "P$2_P$2") (pintype "bidirectional"))
    )
    (net (code "77") (name "unconnected-(J4-PadP$3)") (class "Default")
      (node (ref "J4") (pin "P$3") (pinfunction "P$3_P$3") (pintype "bidirectional"))
    )
    (net (code "78") (name "unconnected-(J4-PadP$8)") (class "Default")
      (node (ref "J4") (pin "P$8") (pinfunction "P$8_P$8") (pintype "bidirectional"))
    )
    (net (code "79") (name "unconnected-(J7-PadP$6)") (class "Default")
      (node (ref "J7") (pin "P$6") (pinfunction "P$6_P$6") (pintype "bidirectional"))
    )
    (net (code "80") (name "unconnected-(U2-P$1{slash}DPIO{slash}1A-Pad1)") (class "Default")
      (node (ref "U2") (pin "1") (pinfunction "P$1/DPIO/1A_1") (pintype "bidirectional"))
    )
    (net (code "81") (name "unconnected-(U2-P$2{slash}DPIO{slash}1B-Pad2)") (class "Default")
      (node (ref "U2") (pin "2") (pinfunction "P$2/DPIO/1B_2") (pintype "bidirectional"))
    )
    (net (code "82") (name "unconnected-(U2-P$3{slash}DPIO{slash}2A-Pad3)") (class "Default")
      (node (ref "U2") (pin "3") (pinfunction "P$3/DPIO/2A_3") (pintype "bidirectional"))
    )
    (net (code "83") (name "unconnected-(U2-P$4{slash}DPIO{slash}2B-Pad4)") (class "Default")
      (node (ref "U2") (pin "4") (pinfunction "P$4/DPIO/2B_4") (pintype "bidirectional"))
    )
    (net (code "84") (name "unconnected-(U2-P$7{slash}DPIO{slash}3A-Pad7)") (class "Default")
      (node (ref "U2") (pin "7") (pinfunction "P$7/DPIO/3A_7") (pintype "bidirectional"))
    )
    (net (code "85") (name "unconnected-(U2-P$8{slash}DPIO{slash}3B-Pad8)") (class "Default")
      (node (ref "U2") (pin "8") (pinfunction "P$8/DPIO/3B_8") (pintype "bidirectional"))
    )
    (net (code "86") (name "unconnected-(U2-P$9{slash}DPIO{slash}5A-Pad9)") (class "Default")
      (node (ref "U2") (pin "9") (pinfunction "P$9/DPIO/5A_9") (pintype "bidirectional"))
    )
    (net (code "87") (name "unconnected-(U2-P$10{slash}DPIO{slash}5B-Pad10)") (class "Default")
      (node (ref "U2") (pin "10") (pinfunction "P$10/DPIO/5B_10") (pintype "bidirectional"))
    )
    (net (code "88") (name "unconnected-(U2-P$12{slash}DPIO{slash}6A-Pad12)") (class "Default")
      (node (ref "U2") (pin "12") (pinfunction "P$12/DPIO/6A_12") (pintype "bidirectional"))
    )
    (net (code "89") (name "unconnected-(U2-P$20{slash}DPIO{slash}10A-Pad20)") (class "Default")
      (node (ref "U2") (pin "20") (pinfunction "P$20/DPIO/10A_20") (pintype "bidirectional"))
    )
    (net (code "90") (name "unconnected-(U2-P$21{slash}DPIO{slash}10B-Pad21)") (class "Default")
      (node (ref "U2") (pin "21") (pinfunction "P$21/DPIO/10B_21") (pintype "bidirectional"))
    )
    (net (code "91") (name "unconnected-(U2-P$24{slash}DPIO{slash}12A-Pad24)") (class "Default")
      (node (ref "U2") (pin "24") (pinfunction "P$24/DPIO/12A_24") (pintype "bidirectional"))
    )
    (net (code "92") (name "unconnected-(U2-P$25{slash}DPIO{slash}12B-Pad25)") (class "Default")
      (node (ref "U2") (pin "25") (pinfunction "P$25/DPIO/12B_25") (pintype "bidirectional"))
    )
    (net (code "93") (name "unconnected-(U2-P$51{slash}PIO-Pad51)") (class "Default")
      (node (ref "U2") (pin "51") (pinfunction "P$51/PIO_51") (pintype "bidirectional"))
    )
    (net (code "94") (name "unconnected-(U2-P$52{slash}PIO-Pad52)") (class "Default")
      (node (ref "U2") (pin "52") (pinfunction "P$52/PIO_52") (pintype "bidirectional"))
    )
    (net (code "95") (name "unconnected-(U2-P$53{slash}PIO-Pad53)") (class "Default")
      (node (ref "U2") (pin "53") (pinfunction "P$53/PIO_53") (pintype "bidirectional"))
    )
    (net (code "96") (name "unconnected-(U2-P$54{slash}PIO-Pad54)") (class "Default")
      (node (ref "U2") (pin "54") (pinfunction "P$54/PIO_54") (pintype "bidirectional"))
    )
    (net (code "97") (name "unconnected-(U2-P$56{slash}PIO-Pad56)") (class "Default")
      (node (ref "U2") (pin "56") (pinfunction "P$56/PIO_56") (pintype "bidirectional"))
    )
    (net (code "98") (name "unconnected-(U2-P$57{slash}PIO-Pad57)") (class "Default")
      (node (ref "U2") (pin "57") (pinfunction "P$57/PIO_57") (pintype "bidirectional"))
    )
    (net (code "99") (name "unconnected-(U2-P$59{slash}PIO-Pad59)") (class "Default")
      (node (ref "U2") (pin "59") (pinfunction "P$59/PIO_59") (pintype "bidirectional"))
    )
    (net (code "100") (name "unconnected-(U2-P$60{slash}PIO-Pad60)") (class "Default")
      (node (ref "U2") (pin "60") (pinfunction "P$60/PIO_60") (pintype "bidirectional"))
    )
    (net (code "101") (name "unconnected-(U2-P$62{slash}GBIN{slash}PIO-Pad62)") (class "Default")
      (node (ref "U2") (pin "62") (pinfunction "P$62/GBIN/PIO_62") (pintype "bidirectional"))
    )
    (net (code "102") (name "unconnected-(U2-P$63{slash}GBIN{slash}PIO-Pad63)") (class "Default")
      (node (ref "U2") (pin "63") (pinfunction "P$63/GBIN/PIO_63") (pintype "bidirectional"))
    )
    (net (code "103") (name "unconnected-(U2-P$64{slash}PIO-Pad64)") (class "Default")
      (node (ref "U2") (pin "64") (pinfunction "P$64/PIO_64") (pintype "bidirectional"))
    )
    (net (code "104") (name "unconnected-(U2-P$65{slash}PIO-Pad65)") (class "Default")
      (node (ref "U2") (pin "65") (pinfunction "P$65/PIO_65") (pintype "bidirectional"))
    )
    (net (code "105") (name "unconnected-(U2-P$66{slash}PIO-Pad66)") (class "Default")
      (node (ref "U2") (pin "66") (pinfunction "P$66/PIO_66") (pintype "bidirectional"))
    )
    (net (code "106") (name "unconnected-(U2-P$68{slash}PIO-Pad68)") (class "Default")
      (node (ref "U2") (pin "68") (pinfunction "P$68/PIO_68") (pintype "bidirectional"))
    )
    (net (code "107") (name "unconnected-(U2-P$69{slash}PIO-Pad69)") (class "Default")
      (node (ref "U2") (pin "69") (pinfunction "P$69/PIO_69") (pintype "bidirectional"))
    )
    (net (code "108") (name "unconnected-(U2-P$71{slash}PIO-Pad71)") (class "Default")
      (node (ref "U2") (pin "71") (pinfunction "P$71/PIO_71") (pintype "bidirectional"))
    )
    (net (code "109") (name "unconnected-(U2-P$72{slash}PIO-Pad72)") (class "Default")
      (node (ref "U2") (pin "72") (pinfunction "P$72/PIO_72") (pintype "bidirectional"))
    )
    (net (code "110") (name "unconnected-(U2-P$73{slash}PIO-Pad73)") (class "Default")
      (node (ref "U2") (pin "73") (pinfunction "P$73/PIO_73") (pintype "bidirectional"))
    )
    (net (code "111") (name "unconnected-(U2-P$74{slash}PIO-Pad74)") (class "Default")
      (node (ref "U2") (pin "74") (pinfunction "P$74/PIO_74") (pintype "bidirectional"))
    )
    (net (code "112") (name "unconnected-(U2-P$76{slash}VPPFAST-Pad76)") (class "Default")
      (node (ref "U2") (pin "76") (pinfunction "P$76/VPPFAST_76") (pintype "bidirectional"))
    )
    (net (code "113") (name "unconnected-(U2-P$78{slash}PIO-Pad78)") (class "Default")
      (node (ref "U2") (pin "78") (pinfunction "P$78/PIO_78") (pintype "bidirectional"))
    )
    (net (code "114") (name "unconnected-(U2-P$79{slash}PIO-Pad79)") (class "Default")
      (node (ref "U2") (pin "79") (pinfunction "P$79/PIO_79") (pintype "bidirectional"))
    )
    (net (code "115") (name "unconnected-(U2-P$80{slash}PIO-Pad80)") (class "Default")
      (node (ref "U2") (pin "80") (pinfunction "P$80/PIO_80") (pintype "bidirectional"))
    )
    (net (code "116") (name "unconnected-(U2-P$81{slash}PIO-Pad81)") (class "Default")
      (node (ref "U2") (pin "81") (pinfunction "P$81/PIO_81") (pintype "bidirectional"))
    )
    (net (code "117") (name "unconnected-(U2-P$82{slash}PIO-Pad82)") (class "Default")
      (node (ref "U2") (pin "82") (pinfunction "P$82/PIO_82") (pintype "bidirectional"))
    )
    (net (code "118") (name "unconnected-(U2-P$83{slash}PIO-Pad83)") (class "Default")
      (node (ref "U2") (pin "83") (pinfunction "P$83/PIO_83") (pintype "bidirectional"))
    )
    (net (code "119") (name "unconnected-(U2-P$85{slash}PIO-Pad85)") (class "Default")
      (node (ref "U2") (pin "85") (pinfunction "P$85/PIO_85") (pintype "bidirectional"))
    )
    (net (code "120") (name "unconnected-(U2-P$86{slash}PIO-Pad86)") (class "Default")
      (node (ref "U2") (pin "86") (pinfunction "P$86/PIO_86") (pintype "bidirectional"))
    )
    (net (code "121") (name "unconnected-(U2-P$87{slash}PIO-Pad87)") (class "Default")
      (node (ref "U2") (pin "87") (pinfunction "P$87/PIO_87") (pintype "bidirectional"))
    )
    (net (code "122") (name "unconnected-(U2-P$89{slash}GBIN{slash}PIO-Pad89)") (class "Default")
      (node (ref "U2") (pin "89") (pinfunction "P$89/GBIN/PIO_89") (pintype "bidirectional"))
    )
    (net (code "123") (name "unconnected-(U2-P$90{slash}GBIN{slash}PIO-Pad90)") (class "Default")
      (node (ref "U2") (pin "90") (pinfunction "P$90/GBIN/PIO_90") (pintype "bidirectional"))
    )
    (net (code "124") (name "unconnected-(U2-P$91{slash}PIO-Pad91)") (class "Default")
      (node (ref "U2") (pin "91") (pinfunction "P$91/PIO_91") (pintype "bidirectional"))
    )
    (net (code "125") (name "unconnected-(U2-P$93{slash}PIO-Pad93)") (class "Default")
      (node (ref "U2") (pin "93") (pinfunction "P$93/PIO_93") (pintype "bidirectional"))
    )
    (net (code "126") (name "unconnected-(U2-P$94{slash}PIO-Pad94)") (class "Default")
      (node (ref "U2") (pin "94") (pinfunction "P$94/PIO_94") (pintype "bidirectional"))
    )
    (net (code "127") (name "unconnected-(U2-P$95{slash}PIO-Pad95)") (class "Default")
      (node (ref "U2") (pin "95") (pinfunction "P$95/PIO_95") (pintype "bidirectional"))
    )
    (net (code "128") (name "unconnected-(U2-P$96{slash}PIO-Pad96)") (class "Default")
      (node (ref "U2") (pin "96") (pinfunction "P$96/PIO_96") (pintype "bidirectional"))
    )
    (net (code "129") (name "unconnected-(U2-P$97{slash}PIO-Pad97)") (class "Default")
      (node (ref "U2") (pin "97") (pinfunction "P$97/PIO_97") (pintype "bidirectional"))
    )
    (net (code "130") (name "unconnected-(U2-P$99{slash}PIO-Pad99)") (class "Default")
      (node (ref "U2") (pin "99") (pinfunction "P$99/PIO_99") (pintype "bidirectional"))
    )
    (net (code "131") (name "unconnected-(U2-P$100{slash}PIO-Pad100)") (class "Default")
      (node (ref "U2") (pin "100") (pinfunction "P$100/PIO_100") (pintype "bidirectional"))
    )
  )
)
